# Enclosure_85x58_SP.net
KiCad netlist of a schematic drawn in EAGLE
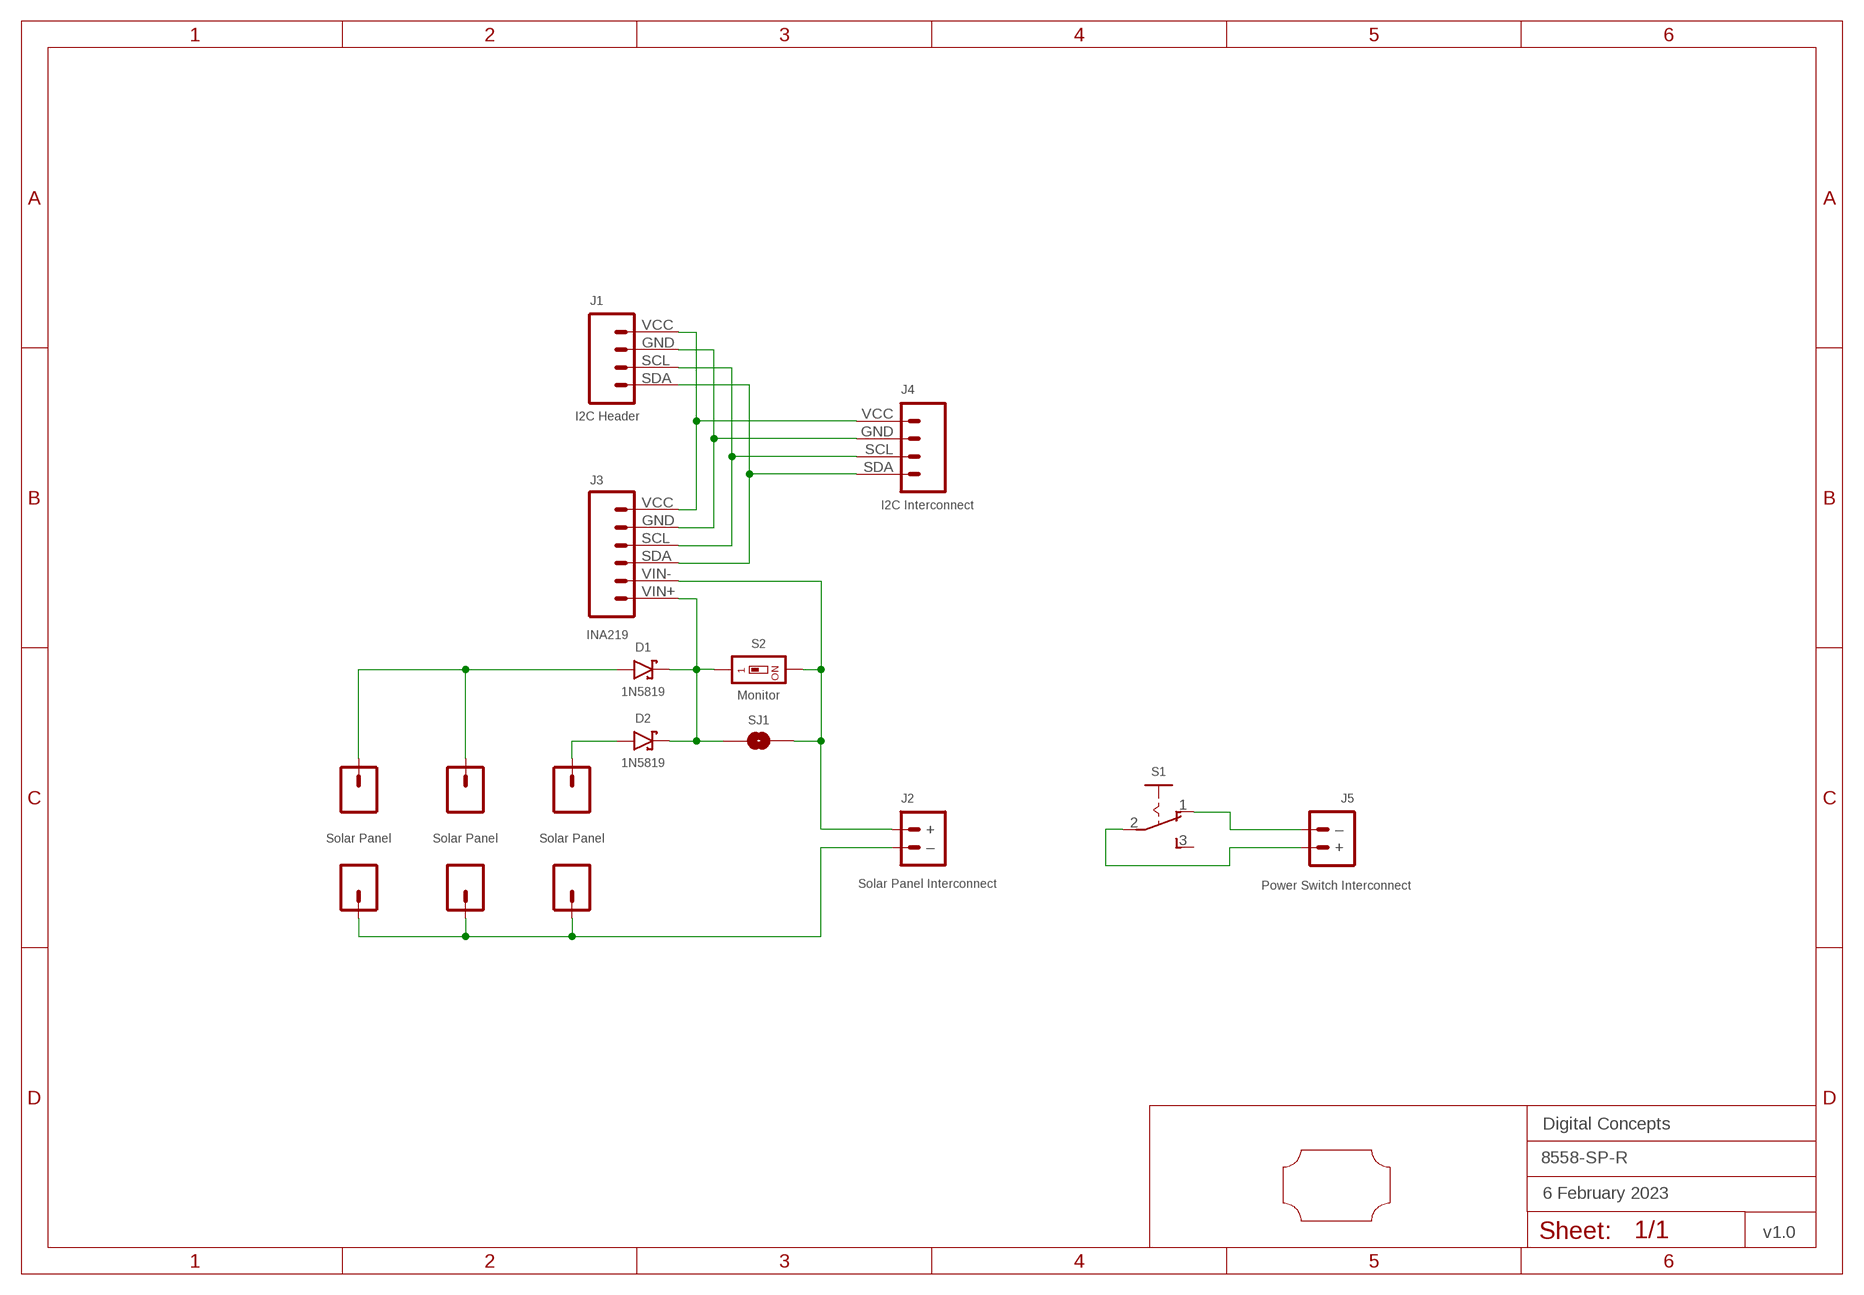
[diagram p0: schematic, sheet 1]

(export (version "E")
  (design (tool "Eeschema 10.0.6"))
  (components
    (comp (ref "+")
      (value "Solar Panel")
      (footprint "eagle-import:PAD-SMD-GENERIC")
      (libsource (lib "eagle-import") (part "PAD-SMD-GENERIC-SQUARE"))
    )
    (comp (ref "+1")
      (value "Solar Panel")
      (footprint "eagle-import:PAD-SMD-GENERIC")
      (libsource (lib "eagle-import") (part "PAD-SMD-GENERIC-SQUARE"))
    )
    (comp (ref "+2")
      (value "Solar Panel")
      (footprint "eagle-import:PAD-SMD-GENERIC")
      (libsource (lib "eagle-import") (part "PAD-SMD-GENERIC-SQUARE"))
    )
    (comp (ref "-")
      (value "Solar Panel")
      (footprint "eagle-import:PAD-SMD-GENERIC")
      (libsource (lib "eagle-import") (part "PAD-SMD-GENERIC-SQUARE"))
    )
    (comp (ref "-1")
      (value "Solar Panel")
      (footprint "eagle-import:PAD-SMD-GENERIC")
      (libsource (lib "eagle-import") (part "PAD-SMD-GENERIC-SQUARE"))
    )
    (comp (ref "-2")
      (value "Solar Panel")
      (footprint "eagle-import:PAD-SMD-GENERIC")
      (libsource (lib "eagle-import") (part "PAD-SMD-GENERIC-SQUARE"))
    )
    (comp (ref "D1")
      (value "1N5819")
      (footprint "eagle-import:SOD-123")
      (libsource (lib "eagle-import") (part "DIODE-SCHOTTKY-1N5819"))
    )
    (comp (ref "D2")
      (value "1N5819")
      (footprint "eagle-import:SOD-123")
      (libsource (lib "eagle-import") (part "DIODE-SCHOTTKY-1N5819"))
    )
    (comp (ref "J1")
      (value "I2C Header")
      (footprint "eagle-import:CONN_04-I2C")
      (libsource (lib "eagle-import") (part "HEADER-1X4-I2C"))
    )
    (comp (ref "J2")
      (value "Solar Panel Interconnect")
      (footprint "eagle-import:JST-PH2.0-2-HORIZONTAL")
      (libsource (lib "eagle-import") (part "JST-PH2.0-2-HORIZONTALJST-PTH-2"))
    )
    (comp (ref "J3")
      (value "INA219")
      (footprint "eagle-import:CONN_06-INA219")
      (libsource (lib "eagle-import") (part "INA219-I2C-MODULE"))
    )
    (comp (ref "J4")
      (value "I2C Interconnect")
      (footprint "eagle-import:JST-PH2.0-4-HORIZONTAL")
      (libsource (lib "eagle-import") (part "JST-PH2.0-4-I2C-HORIZONTAL"))
    )
    (comp (ref "J5")
      (value "Power Switch Interconnect")
      (footprint "eagle-import:JST-PH2.0-2-HORIZONTAL")
      (libsource (lib "eagle-import") (part "JST-PH2.0-2-HORIZONTALJST-PTH-2"))
    )
    (comp (ref "S1")
      (value "SWITCH-SLIDE-SPDT")
      (footprint "eagle-import:SWITCH-SPDT-PTH")
      (libsource (lib "eagle-import") (part "SWITCH-SLIDE-SPDT"))
    )
    (comp (ref "S2")
      (value "Monitor")
      (footprint "eagle-import:SMD-001")
      (libsource (lib "eagle-import") (part "SWITCH-DIP-SWS001"))
    )
    (comp (ref "SJ1") (value "SJ") (footprint "eagle-import:SJ") (libsource (lib "eagle-import") (part "SJ")))
    (comp (ref "U$1")
      (value "PROTO-28X18-SP")
      (footprint "eagle-import:PROTO-28X18-SP")
      (libsource (lib "eagle-import") (part "PROTO-28X18-SP"))
    )
  )
  (nets
    (net (code "1") (name "Net-(+-1)") (class "Default")
      (node (ref "+") (pin "P$1") (pinfunction "1_P$1") (pintype "passive"))
      (node (ref "D2") (pin "A") (pinfunction "A_A") (pintype "passive"))
    )
    (net (code "2") (name "Net-(+1-1)") (class "Default")
      (node (ref "+1") (pin "P$1") (pinfunction "1_P$1") (pintype "passive"))
      (node (ref "+2") (pin "P$1") (pinfunction "1_P$1") (pintype "passive"))
      (node (ref "D1") (pin "A") (pinfunction "A_A") (pintype "passive"))
    )
    (net (code "3") (name "Net-(--1)") (class "Default")
      (node (ref "-") (pin "P$1") (pinfunction "1_P$1") (pintype "passive"))
      (node (ref "-1") (pin "P$1") (pinfunction "1_P$1") (pintype "passive"))
      (node (ref "-2") (pin "P$1") (pinfunction "1_P$1") (pintype "passive"))
      (node (ref "J2") (pin "2") (pinfunction "–_2") (pintype "power_in"))
    )
    (net (code "4") (name "Net-(J1-1)") (class "Default")
      (node (ref "J1") (pin "VCC") (pinfunction "1_VCC") (pintype "passive"))
      (node (ref "J3") (pin "VCC") (pinfunction "1_VCC") (pintype "passive"))
      (node (ref "J4") (pin "VCC") (pinfunction "4_VCC") (pintype "passive"))
    )
    (net (code "5") (name "Net-(J1-2)") (class "Default")
      (node (ref "J1") (pin "GND") (pinfunction "2_GND") (pintype "passive"))
      (node (ref "J3") (pin "GND") (pinfunction "2_GND") (pintype "passive"))
      (node (ref "J4") (pin "GND") (pinfunction "3_GND") (pintype "passive"))
    )
    (net (code "6") (name "Net-(J1-3)") (class "Default")
      (node (ref "J1") (pin "SCL") (pinfunction "3_SCL") (pintype "passive"))
      (node (ref "J3") (pin "SCL") (pinfunction "3_SCL") (pintype "passive"))
      (node (ref "J4") (pin "SCL") (pinfunction "2_SCL") (pintype "passive"))
    )
    (net (code "7") (name "Net-(J1-4)") (class "Default")
      (node (ref "J1") (pin "SDA") (pinfunction "4_SDA") (pintype "passive"))
      (node (ref "J3") (pin "SDA") (pinfunction "4_SDA") (pintype "passive"))
      (node (ref "J4") (pin "SDA") (pinfunction "1_SDA") (pintype "passive"))
    )
    (net (code "8") (name "Net-(J2-+)") (class "Default")
      (node (ref "J2") (pin "1") (pinfunction "+_1") (pintype "power_in"))
      (node (ref "J3") (pin "VIN-") (pinfunction "5_VIN-") (pintype "passive"))
      (node (ref "S2") (pin "2") (pinfunction "2_2") (pintype "passive"))
      (node (ref "SJ1") (pin "2") (pinfunction "2_2") (pintype "passive"))
    )
    (net (code "9") (name "Net-(J3-6)") (class "Default")
      (node (ref "D1") (pin "C") (pinfunction "C_C") (pintype "passive"))
      (node (ref "D2") (pin "C") (pinfunction "C_C") (pintype "passive"))
      (node (ref "J3") (pin "VIN+") (pinfunction "6_VIN+") (pintype "passive"))
      (node (ref "S2") (pin "1") (pinfunction "1_1") (pintype "passive"))
      (node (ref "SJ1") (pin "1") (pinfunction "1_1") (pintype "passive"))
    )
    (net (code "10") (name "Net-(J5-+)") (class "Default")
      (node (ref "J5") (pin "1") (pinfunction "+_1") (pintype "power_in"))
      (node (ref "S1") (pin "2") (pinfunction "P_2") (pintype "passive"))
    )
    (net (code "11") (name "Net-(J5-–)") (class "Default")
      (node (ref "J5") (pin "2") (pinfunction "–_2") (pintype "power_in"))
      (node (ref "S1") (pin "1") (pinfunction "O_1") (pintype "passive"))
    )
    (net (code "12") (name "unconnected-(S1-S-Pad3)") (class "Default")
      (node (ref "S1") (pin "3") (pinfunction "S_3") (pintype "passive"))
    )
  )
)
